# MSP430G2553_MCU.net
KiCad netlist of a schematic drawn in Altium Designer
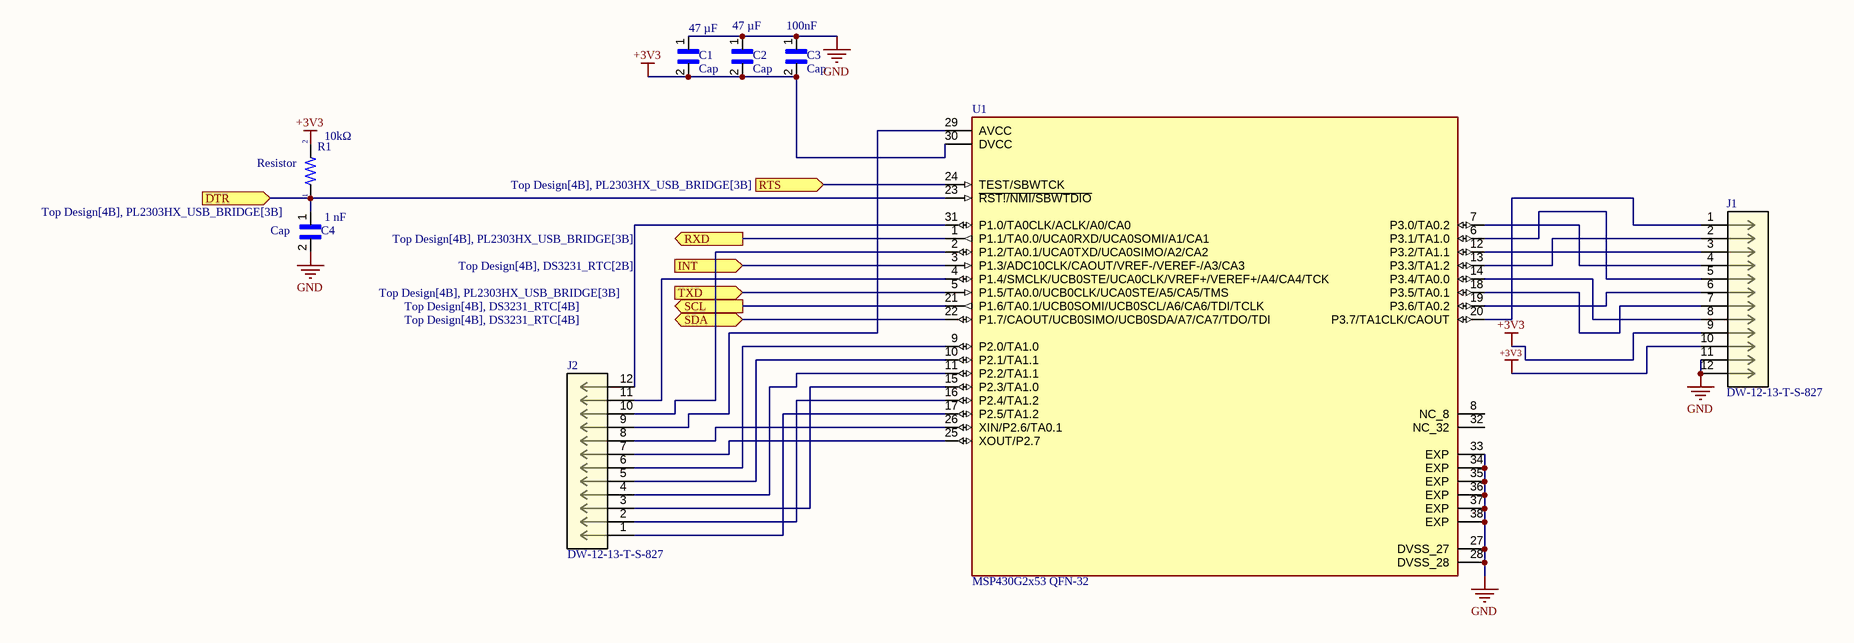
[diagram p0: MSP430G2553_MCU.SchDoc]

(export (version "E")
  (design (tool "Eeschema 10.0.6"))
  (components
    (comp (ref "C1")
      (value "Cap")
      (footprint "Cap_0805")
      (fields (field (name "CAPACITANCE") "47 µF"))
      (libsource (lib "SLT_DL_Discreate") (part "Cap"))
    )
    (comp (ref "C2")
      (value "Cap")
      (footprint "Cap_0805")
      (fields (field (name "CAPACITANCE") "47 µF"))
      (libsource (lib "SLT_DL_Discreate") (part "Cap"))
    )
    (comp (ref "C3")
      (value "Cap")
      (footprint "Cap_0805")
      (fields (field (name "CAPACITANCE") "100nF"))
      (libsource (lib "SLT_DL_Discreate") (part "Cap"))
    )
    (comp (ref "C4")
      (value "Cap")
      (footprint "Cap_0805")
      (fields (field (name "CAPACITANCE") "1 nF"))
      (libsource (lib "SLT_DL_Discreate") (part "Cap"))
    )
    (comp (ref "J1")
      (value "DW-12-13-T-S-827")
      (footprint "CONN12-07-F-S-200_SAI")
      (description "No Description Available")
      (libsource (lib "DW-12-13-T-S-827") (part "DW-12-13-T-S-827"))
    )
    (comp (ref "J2")
      (value "DW-12-13-T-S-827")
      (footprint "CONN12-07-F-S-200_SAI")
      (description "No Description Available")
      (libsource (lib "") (part "DW-12-13-T-S-827_1"))
    )
    (comp (ref "R1")
      (value "Resistor")
      (footprint "Res_0603")
      (fields (field (name "PARAMETER 1") "10kΩ"))
      (libsource (lib "SLT_DL_Discreate") (part "Resistor"))
    )
    (comp (ref "U1")
      (value "MSP430G2x53 QFN-32")
      (footprint "MSP430G2x53_QFN")
      (description "QFN-32-EP(5x5) Microcontroller Units (MCUs/MPUs/SOCs) ROHS. Texas Instruments.")
      (fields (field (name "MP") "MSP430G2553IRHB32R"))
      (libsource (lib "SLT_DL_Device") (part "MSP430G2x53 QFN-32"))
    )
  )
  (nets
    (net (code "1") (name "+3V3") (class "Default")
      (node (ref "C1") (pin "2") (pinfunction "2_2") (pintype "passive"))
      (node (ref "C2") (pin "2") (pinfunction "2_2") (pintype "passive"))
      (node (ref "C3") (pin "2") (pinfunction "2_2") (pintype "passive"))
      (node (ref "J1") (pin "10") (pinfunction "10_10") (pintype "passive"))
      (node (ref "J1") (pin "9") (pinfunction "9_9") (pintype "passive"))
      (node (ref "R1") (pin "2") (pinfunction "2_2") (pintype "passive"))
      (node (ref "U1") (pin "30") (pinfunction "DVCC_30") (pintype "power_in"))
    )
    (net (code "2") (name "/DTR") (class "Default")
      (node (ref "C4") (pin "1") (pinfunction "1_1") (pintype "passive"))
      (node (ref "R1") (pin "1") (pinfunction "1_1") (pintype "passive"))
      (node (ref "U1") (pin "23") (pinfunction "~{RST!/NMI/SBWTDIO}_23") (pintype "input"))
    )
    (net (code "3") (name "/INT") (class "Default")
      (node (ref "U1") (pin "3") (pinfunction "P1.3/ADC10CLK/CAOUT/VREF-/VEREF-/A3/CA3_3") (pintype "input"))
    )
    (net (code "4") (name "/RTS") (class "Default")
      (node (ref "U1") (pin "24") (pinfunction "TEST/SBWTCK_24") (pintype "input"))
    )
    (net (code "5") (name "/RXD") (class "Default")
      (node (ref "U1") (pin "1") (pinfunction "P1.1/TA0.0/UCA0RXD/UCA0SOMI/A1/CA1_1") (pintype "output"))
    )
    (net (code "6") (name "/SCL") (class "Default")
      (node (ref "U1") (pin "21") (pinfunction "P1.6/TA0.1/UCB0SOMI/UCB0SCL/A6/CA6/TDI/TCLK_21") (pintype "output"))
    )
    (net (code "7") (name "/SDA") (class "Default")
      (node (ref "U1") (pin "22") (pinfunction "P1.7/CAOUT/UCB0SIMO/UCB0SDA/A7/CA7/TDO/TDI_22") (pintype "bidirectional"))
    )
    (net (code "8") (name "/TXD") (class "Default")
      (node (ref "U1") (pin "5") (pinfunction "P1.5/TA0.0/UCB0CLK/UCA0STE/A5/CA5/TMS_5") (pintype "input"))
    )
    (net (code "9") (name "GND") (class "Default")
      (node (ref "C1") (pin "1") (pinfunction "1_1") (pintype "passive"))
      (node (ref "C2") (pin "1") (pinfunction "1_1") (pintype "passive"))
      (node (ref "C3") (pin "1") (pinfunction "1_1") (pintype "passive"))
      (node (ref "C4") (pin "2") (pinfunction "2_2") (pintype "passive"))
      (node (ref "J1") (pin "11") (pinfunction "11_11") (pintype "passive"))
      (node (ref "J1") (pin "12") (pinfunction "12_12") (pintype "passive"))
      (node (ref "U1") (pin "27") (pinfunction "DVSS_27_27") (pintype "power_in"))
      (node (ref "U1") (pin "28") (pinfunction "DVSS_28_28") (pintype "power_in"))
      (node (ref "U1") (pin "33") (pinfunction "EXP_33") (pintype "passive"))
      (node (ref "U1") (pin "34") (pinfunction "EXP_34") (pintype "passive"))
      (node (ref "U1") (pin "35") (pinfunction "EXP_35") (pintype "passive"))
      (node (ref "U1") (pin "36") (pinfunction "EXP_36") (pintype "passive"))
      (node (ref "U1") (pin "37") (pinfunction "EXP_37") (pintype "passive"))
      (node (ref "U1") (pin "38") (pinfunction "EXP_38") (pintype "passive"))
    )
    (net (code "10") (name "Net-(U1-AVCC)") (class "Default")
      (node (ref "J2") (pin "9") (pinfunction "9_9") (pintype "passive"))
      (node (ref "U1") (pin "29") (pinfunction "AVCC_29") (pintype "power_in"))
    )
    (net (code "11") (name "Net-(U1-P1.0{slash}TA0CLK{slash}ACLK{slash}A0{slash}CA0)") (class "Default")
      (node (ref "J2") (pin "12") (pinfunction "12_12") (pintype "passive"))
      (node (ref "U1") (pin "31") (pinfunction "P1.0/TA0CLK/ACLK/A0/CA0_31") (pintype "bidirectional"))
    )
    (net (code "12") (name "Net-(U1-P1.2{slash}TA0.1{slash}UCA0TXD{slash}UCA0SIMO{slash}A2{slash}CA2)") (class "Default")
      (node (ref "J2") (pin "10") (pinfunction "10_10") (pintype "passive"))
      (node (ref "U1") (pin "2") (pinfunction "P1.2/TA0.1/UCA0TXD/UCA0SIMO/A2/CA2_2") (pintype "bidirectional"))
    )
    (net (code "13") (name "Net-(U1-P1.4{slash}SMCLK{slash}UCB0STE{slash}UCA0CLK{slash}VREF+{slash}VEREF+{slash}A4{slash}CA4{slash}TCK)") (class "Default")
      (node (ref "J2") (pin "11") (pinfunction "11_11") (pintype "passive"))
      (node (ref "U1") (pin "4") (pinfunction "P1.4/SMCLK/UCB0STE/UCA0CLK/VREF+/VEREF+/A4/CA4/TCK_4") (pintype "bidirectional"))
    )
    (net (code "14") (name "Net-(U1-P2.0{slash}TA1.0)") (class "Default")
      (node (ref "J2") (pin "6") (pinfunction "6_6") (pintype "passive"))
      (node (ref "U1") (pin "9") (pinfunction "P2.0/TA1.0_9") (pintype "bidirectional"))
    )
    (net (code "15") (name "Net-(U1-P2.1{slash}TA1.1)") (class "Default")
      (node (ref "J2") (pin "5") (pinfunction "5_5") (pintype "passive"))
      (node (ref "U1") (pin "10") (pinfunction "P2.1/TA1.1_10") (pintype "bidirectional"))
    )
    (net (code "16") (name "Net-(U1-P2.2{slash}TA1.1)") (class "Default")
      (node (ref "J2") (pin "4") (pinfunction "4_4") (pintype "passive"))
      (node (ref "U1") (pin "11") (pinfunction "P2.2/TA1.1_11") (pintype "bidirectional"))
    )
    (net (code "17") (name "Net-(U1-P2.3{slash}TA1.0)") (class "Default")
      (node (ref "J2") (pin "3") (pinfunction "3_3") (pintype "passive"))
      (node (ref "U1") (pin "15") (pinfunction "P2.3/TA1.0_15") (pintype "bidirectional"))
    )
    (net (code "18") (name "Net-(U1-P2.4{slash}TA1.2)") (class "Default")
      (node (ref "J2") (pin "2") (pinfunction "2_2") (pintype "passive"))
      (node (ref "U1") (pin "16") (pinfunction "P2.4/TA1.2_16") (pintype "bidirectional"))
    )
    (net (code "19") (name "Net-(U1-P2.5{slash}TA1.2)") (class "Default")
      (node (ref "J2") (pin "1") (pinfunction "1_1") (pintype "passive"))
      (node (ref "U1") (pin "17") (pinfunction "P2.5/TA1.2_17") (pintype "bidirectional"))
    )
    (net (code "20") (name "Net-(U1-P3.0{slash}TA0.2)") (class "Default")
      (node (ref "J1") (pin "4") (pinfunction "4_4") (pintype "passive"))
      (node (ref "U1") (pin "7") (pinfunction "P3.0/TA0.2_7") (pintype "bidirectional"))
    )
    (net (code "21") (name "Net-(U1-P3.1{slash}TA1.0)") (class "Default")
      (node (ref "J1") (pin "5") (pinfunction "5_5") (pintype "passive"))
      (node (ref "U1") (pin "6") (pinfunction "P3.1/TA1.0_6") (pintype "bidirectional"))
    )
    (net (code "22") (name "Net-(U1-P3.2{slash}TA1.1)") (class "Default")
      (node (ref "J1") (pin "3") (pinfunction "3_3") (pintype "passive"))
      (node (ref "U1") (pin "12") (pinfunction "P3.2/TA1.1_12") (pintype "bidirectional"))
    )
    (net (code "23") (name "Net-(U1-P3.3{slash}TA1.2)") (class "Default")
      (node (ref "J1") (pin "2") (pinfunction "2_2") (pintype "passive"))
      (node (ref "U1") (pin "13") (pinfunction "P3.3/TA1.2_13") (pintype "bidirectional"))
    )
    (net (code "24") (name "Net-(U1-P3.4{slash}TA0.0)") (class "Default")
      (node (ref "J1") (pin "8") (pinfunction "8_8") (pintype "passive"))
      (node (ref "U1") (pin "14") (pinfunction "P3.4/TA0.0_14") (pintype "bidirectional"))
    )
    (net (code "25") (name "Net-(U1-P3.5{slash}TA0.1)") (class "Default")
      (node (ref "J1") (pin "7") (pinfunction "7_7") (pintype "passive"))
      (node (ref "U1") (pin "18") (pinfunction "P3.5/TA0.1_18") (pintype "bidirectional"))
    )
    (net (code "26") (name "Net-(U1-P3.6{slash}TA0.2)") (class "Default")
      (node (ref "J1") (pin "6") (pinfunction "6_6") (pintype "passive"))
      (node (ref "U1") (pin "19") (pinfunction "P3.6/TA0.2_19") (pintype "bidirectional"))
    )
    (net (code "27") (name "Net-(U1-P3.7{slash}TA1CLK{slash}CAOUT)") (class "Default")
      (node (ref "J1") (pin "1") (pinfunction "1_1") (pintype "passive"))
      (node (ref "U1") (pin "20") (pinfunction "P3.7/TA1CLK/CAOUT_20") (pintype "bidirectional"))
    )
    (net (code "28") (name "Net-(U1-XIN{slash}P2.6{slash}TA0.1)") (class "Default")
      (node (ref "J2") (pin "8") (pinfunction "8_8") (pintype "passive"))
      (node (ref "U1") (pin "26") (pinfunction "XIN/P2.6/TA0.1_26") (pintype "bidirectional"))
    )
    (net (code "29") (name "Net-(U1-XOUT{slash}P2.7)") (class "Default")
      (node (ref "J2") (pin "7") (pinfunction "7_7") (pintype "passive"))
      (node (ref "U1") (pin "25") (pinfunction "XOUT/P2.7_25") (pintype "bidirectional"))
    )
    (net (code "30") (name "unconnected-(U1-NC_8-Pad8)") (class "Default")
      (node (ref "U1") (pin "8") (pinfunction "NC_8_8") (pintype "passive"))
    )
    (net (code "31") (name "unconnected-(U1-NC_32-Pad32)") (class "Default")
      (node (ref "U1") (pin "32") (pinfunction "NC_32_32") (pintype "passive"))
    )
  )
)
